# usbschalter.net
KiCad netlist of a schematic drawn in EAGLE
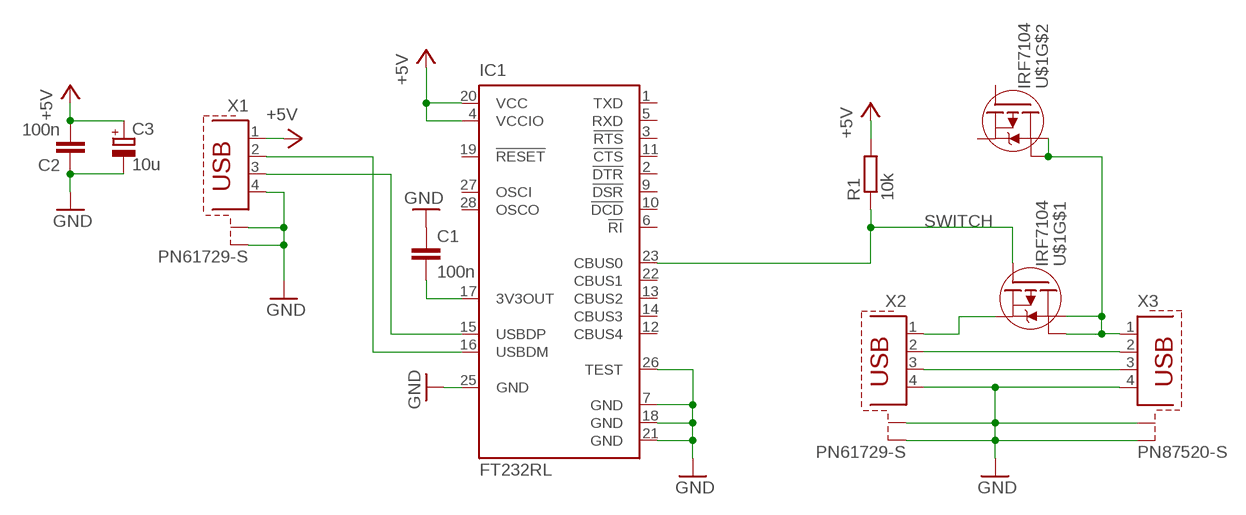
[diagram p0: schematic, sheet 1]

(export (version "E")
  (design (tool "Eeschema 10.0.6"))
  (components
    (comp (ref "C1")
      (value "100n")
      (footprint "eagle-import:C0805")
      (libsource (lib "eagle-import") (part "C-EUC0805"))
    )
    (comp (ref "C2")
      (value "100n")
      (footprint "eagle-import:C0805")
      (libsource (lib "eagle-import") (part "C-EUC0805"))
    )
    (comp (ref "C3")
      (value "10u")
      (footprint "eagle-import:E1,8-4")
      (libsource (lib "eagle-import") (part "CPOL-EUE1.8-4"))
    )
    (comp (ref "IC1")
      (value "FT232RL")
      (footprint "eagle-import:SSOP28")
      (libsource (lib "eagle-import") (part "FT232RL"))
    )
    (comp (ref "R1")
      (value "10k")
      (footprint "eagle-import:R0805")
      (libsource (lib "eagle-import") (part "R-EU_R0805"))
    )
    (comp (ref "U$1")
      (value "IRF7104")
      (footprint "eagle-import:SO8-2")
      (libsource (lib "eagle-import") (part "IRF7104"))
    )
    (comp (ref "X1")
      (value "PN61729-S")
      (footprint "eagle-import:PN61729-S")
      (libsource (lib "eagle-import") (part "PN61729-S"))
    )
    (comp (ref "X2")
      (value "PN61729-S")
      (footprint "eagle-import:PN61729-S")
      (libsource (lib "eagle-import") (part "PN61729-S"))
    )
    (comp (ref "X3")
      (value "PN87520-S")
      (footprint "eagle-import:PN87520-S")
      (libsource (lib "eagle-import") (part "PN87520-S"))
    )
  )
  (nets
    (net (code "1") (name "+5V") (class "Default")
      (node (ref "C2") (pin "2") (pinfunction "2_2") (pintype "passive"))
      (node (ref "C3") (pin "+") (pinfunction "+_+") (pintype "passive"))
      (node (ref "IC1") (pin "20") (pinfunction "VCC_20") (pintype "power_in"))
      (node (ref "IC1") (pin "4") (pinfunction "VCCIO_4") (pintype "power_in"))
      (node (ref "R1") (pin "2") (pinfunction "2_2") (pintype "passive"))
      (node (ref "X1") (pin "1") (pinfunction "1_1") (pintype "passive"))
    )
    (net (code "2") (name "/SWITCH") (class "Default")
      (node (ref "IC1") (pin "23") (pinfunction "CBUS0_23") (pintype "bidirectional"))
      (node (ref "R1") (pin "1") (pinfunction "1_1") (pintype "passive"))
      (node (ref "U$1") (pin "2") (pinfunction "G_2") (pintype "bidirectional"))
    )
    (net (code "3") (name "GND") (class "Default")
      (node (ref "C1") (pin "1") (pinfunction "1_1") (pintype "passive"))
      (node (ref "C2") (pin "1") (pinfunction "1_1") (pintype "passive"))
      (node (ref "C3") (pin "-") (pinfunction "-_-") (pintype "passive"))
      (node (ref "IC1") (pin "18") (pinfunction "GND_18") (pintype "power_in"))
      (node (ref "IC1") (pin "21") (pinfunction "GND_21") (pintype "power_in"))
      (node (ref "IC1") (pin "25") (pinfunction "GND_25") (pintype "power_in"))
      (node (ref "IC1") (pin "26") (pinfunction "TEST_26") (pintype "input"))
      (node (ref "IC1") (pin "7") (pinfunction "GND_7") (pintype "power_in"))
      (node (ref "X1") (pin "4") (pinfunction "4_4") (pintype "passive"))
      (node (ref "X1") (pin "S1") (pinfunction "S1_S1") (pintype "passive"))
      (node (ref "X1") (pin "S2") (pinfunction "S2_S2") (pintype "passive"))
      (node (ref "X2") (pin "4") (pinfunction "4_4") (pintype "passive"))
      (node (ref "X2") (pin "S1") (pinfunction "S1_S1") (pintype "passive"))
      (node (ref "X2") (pin "S2") (pinfunction "S2_S2") (pintype "passive"))
      (node (ref "X3") (pin "4") (pinfunction "4_4") (pintype "passive"))
      (node (ref "X3") (pin "S1") (pinfunction "S1_S1") (pintype "passive"))
      (node (ref "X3") (pin "S2") (pinfunction "S2_S2") (pintype "passive"))
    )
    (net (code "4") (name "Net-(IC1-3V3OUT)") (class "Default")
      (node (ref "C1") (pin "2") (pinfunction "2_2") (pintype "passive"))
      (node (ref "IC1") (pin "17") (pinfunction "3V3OUT_17") (pintype "output"))
    )
    (net (code "5") (name "Net-(IC1-USBDM)") (class "Default")
      (node (ref "IC1") (pin "16") (pinfunction "USBDM_16") (pintype "bidirectional"))
      (node (ref "X1") (pin "2") (pinfunction "2_2") (pintype "passive"))
    )
    (net (code "6") (name "Net-(IC1-USBDP)") (class "Default")
      (node (ref "IC1") (pin "15") (pinfunction "USBDP_15") (pintype "bidirectional"))
      (node (ref "X1") (pin "3") (pinfunction "3_3") (pintype "passive"))
    )
    (net (code "7") (name "Net-(U$1A-D-Pad7)") (class "Default")
      (node (ref "U$1") (pin "5") (pinfunction "D_5") (pintype "bidirectional"))
      (node (ref "U$1") (pin "6") (pinfunction "D_6") (pintype "bidirectional"))
      (node (ref "U$1") (pin "7") (pinfunction "D_7") (pintype "bidirectional"))
      (node (ref "U$1") (pin "8") (pinfunction "D_8") (pintype "bidirectional"))
      (node (ref "X3") (pin "1") (pinfunction "1_1") (pintype "passive"))
    )
    (net (code "8") (name "Net-(U$1A-S)") (class "Default")
      (node (ref "U$1") (pin "1") (pinfunction "S_1") (pintype "bidirectional"))
      (node (ref "X2") (pin "1") (pinfunction "1_1") (pintype "passive"))
    )
    (net (code "9") (name "Net-(X2-Pad2)") (class "Default")
      (node (ref "X2") (pin "2") (pinfunction "2_2") (pintype "passive"))
      (node (ref "X3") (pin "2") (pinfunction "2_2") (pintype "passive"))
    )
    (net (code "10") (name "Net-(X2-Pad3)") (class "Default")
      (node (ref "X2") (pin "3") (pinfunction "3_3") (pintype "passive"))
      (node (ref "X3") (pin "3") (pinfunction "3_3") (pintype "passive"))
    )
    (net (code "11") (name "unconnected-(IC1-CBUS1-Pad22)") (class "Default")
      (node (ref "IC1") (pin "22") (pinfunction "CBUS1_22") (pintype "bidirectional"))
    )
    (net (code "12") (name "unconnected-(IC1-CBUS2-Pad13)") (class "Default")
      (node (ref "IC1") (pin "13") (pinfunction "CBUS2_13") (pintype "bidirectional"))
    )
    (net (code "13") (name "unconnected-(IC1-CBUS3-Pad14)") (class "Default")
      (node (ref "IC1") (pin "14") (pinfunction "CBUS3_14") (pintype "bidirectional"))
    )
    (net (code "14") (name "unconnected-(IC1-CBUS4-Pad12)") (class "Default")
      (node (ref "IC1") (pin "12") (pinfunction "CBUS4_12") (pintype "bidirectional"))
    )
    (net (code "15") (name "unconnected-(IC1-OSCI-Pad27)") (class "Default")
      (node (ref "IC1") (pin "27") (pinfunction "OSCI_27") (pintype "input"))
    )
    (net (code "16") (name "unconnected-(IC1-OSCO-Pad28)") (class "Default")
      (node (ref "IC1") (pin "28") (pinfunction "OSCO_28") (pintype "output"))
    )
    (net (code "17") (name "unconnected-(IC1-RXD-Pad5)") (class "Default")
      (node (ref "IC1") (pin "5") (pinfunction "RXD_5") (pintype "input"))
    )
    (net (code "18") (name "unconnected-(IC1-TXD-Pad1)") (class "Default")
      (node (ref "IC1") (pin "1") (pinfunction "TXD_1") (pintype "output"))
    )
    (net (code "19") (name "unconnected-(IC1-~{CTS}-Pad11)") (class "Default")
      (node (ref "IC1") (pin "11") (pinfunction "~{CTS}_11") (pintype "input"))
    )
    (net (code "20") (name "unconnected-(IC1-~{DCD}-Pad10)") (class "Default")
      (node (ref "IC1") (pin "10") (pinfunction "~{DCD}_10") (pintype "input"))
    )
    (net (code "21") (name "unconnected-(IC1-~{DSR}-Pad9)") (class "Default")
      (node (ref "IC1") (pin "9") (pinfunction "~{DSR}_9") (pintype "input"))
    )
    (net (code "22") (name "unconnected-(IC1-~{DTR}-Pad2)") (class "Default")
      (node (ref "IC1") (pin "2") (pinfunction "~{DTR}_2") (pintype "output"))
    )
    (net (code "23") (name "unconnected-(IC1-~{RESET}-Pad19)") (class "Default")
      (node (ref "IC1") (pin "19") (pinfunction "~{RESET}_19") (pintype "input"))
    )
    (net (code "24") (name "unconnected-(IC1-~{RI}-Pad6)") (class "Default")
      (node (ref "IC1") (pin "6") (pinfunction "~{RI}_6") (pintype "input"))
    )
    (net (code "25") (name "unconnected-(IC1-~{RTS}-Pad3)") (class "Default")
      (node (ref "IC1") (pin "3") (pinfunction "~{RTS}_3") (pintype "output"))
    )
    (net (code "26") (name "unconnected-(U$1B-G-Pad4)") (class "Default")
      (node (ref "U$1") (pin "4") (pinfunction "G_4") (pintype "bidirectional"))
    )
    (net (code "27") (name "unconnected-(U$1B-S-Pad3)") (class "Default")
      (node (ref "U$1") (pin "3") (pinfunction "S_3") (pintype "bidirectional"))
    )
  )
)
